# Arduino-Pro-Mini-CNC.net
KiCad netlist of a schematic drawn in EAGLE
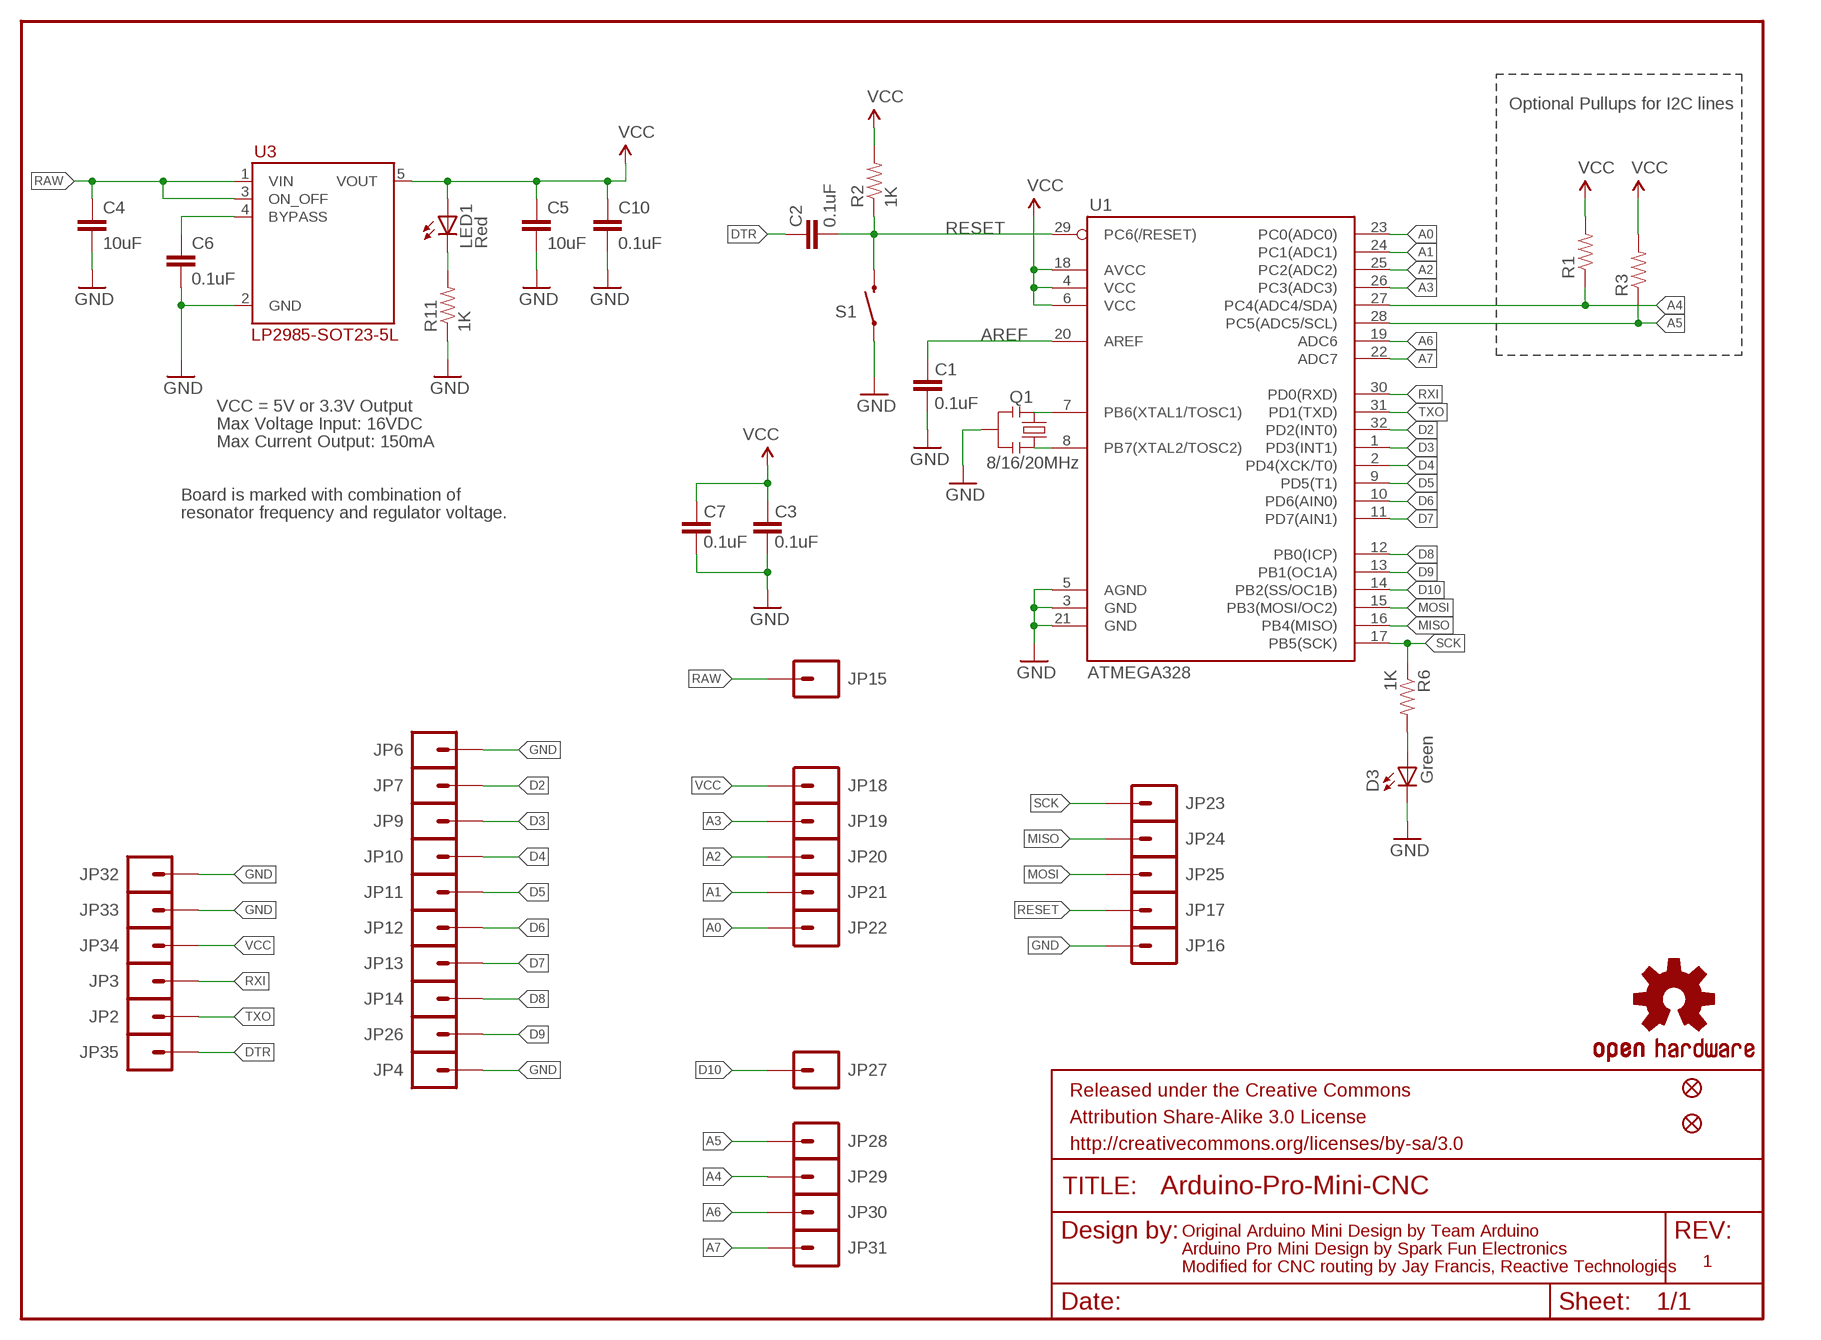
[diagram p0: schematic, sheet 1]

(export (version "E")
  (design (tool "Eeschema 10.0.6"))
  (components
    (comp (ref "C1")
      (value "0.1uF")
      (footprint "eagle-import:0603-CAP")
      (libsource (lib "eagle-import") (part "CAP0603-CAP"))
    )
    (comp (ref "C2")
      (value "0.1uF")
      (footprint "eagle-import:0603-CAP")
      (libsource (lib "eagle-import") (part "CAP0603-CAP"))
    )
    (comp (ref "C3")
      (value "0.1uF")
      (footprint "eagle-import:0603-CAP")
      (libsource (lib "eagle-import") (part "CAP0603-CAP"))
    )
    (comp (ref "C4")
      (value "10uF")
      (footprint "eagle-import:0603-CAP")
      (libsource (lib "eagle-import") (part "CAP0603-CAP"))
    )
    (comp (ref "C5")
      (value "10uF")
      (footprint "eagle-import:0603-CAP")
      (libsource (lib "eagle-import") (part "CAP0603-CAP"))
    )
    (comp (ref "C6")
      (value "0.1uF")
      (footprint "eagle-import:0603-CAP")
      (libsource (lib "eagle-import") (part "CAP0603-CAP"))
    )
    (comp (ref "C7")
      (value "0.1uF")
      (footprint "eagle-import:0603-CAP")
      (libsource (lib "eagle-import") (part "CAP0603-CAP"))
    )
    (comp (ref "C10")
      (value "0.1uF")
      (footprint "eagle-import:0603-CAP")
      (libsource (lib "eagle-import") (part "CAP0603-CAP"))
    )
    (comp (ref "D3")
      (value "Green")
      (footprint "eagle-import:0603-LED-ALT1")
      (libsource (lib "eagle-import") (part "LED"))
    )
    (comp (ref "FRAME1")
      (value "FRAME-LETTER")
      (footprint "eagle-import:CREATIVE_COMMONS")
      (libsource (lib "eagle-import") (part "FRAME-LETTER"))
    )
    (comp (ref "JP2")
      (value "M01SMD_160X40")
      (footprint "eagle-import:PAD-160-040")
      (libsource (lib "eagle-import") (part "M01SMD_160X40"))
    )
    (comp (ref "JP3")
      (value "M01SMD_160X40")
      (footprint "eagle-import:PAD-160-040")
      (libsource (lib "eagle-import") (part "M01SMD_160X40"))
    )
    (comp (ref "JP4")
      (value "M01SMD_160X40")
      (footprint "eagle-import:PAD-160-040")
      (libsource (lib "eagle-import") (part "M01SMD_160X40"))
    )
    (comp (ref "JP5")
      (value "FIDUCIALUFIDUCIAL")
      (footprint "eagle-import:MICRO-FIDUCIAL")
      (libsource (lib "eagle-import") (part "FIDUCIALUFIDUCIAL"))
    )
    (comp (ref "JP6")
      (value "M01SMD_160X40")
      (footprint "eagle-import:PAD-160-040")
      (libsource (lib "eagle-import") (part "M01SMD_160X40"))
    )
    (comp (ref "JP7")
      (value "M01SMD_160X40")
      (footprint "eagle-import:PAD-160-040")
      (libsource (lib "eagle-import") (part "M01SMD_160X40"))
    )
    (comp (ref "JP8")
      (value "FIDUCIALUFIDUCIAL")
      (footprint "eagle-import:MICRO-FIDUCIAL")
      (libsource (lib "eagle-import") (part "FIDUCIALUFIDUCIAL"))
    )
    (comp (ref "JP9")
      (value "M01SMD_160X40")
      (footprint "eagle-import:PAD-160-040")
      (libsource (lib "eagle-import") (part "M01SMD_160X40"))
    )
    (comp (ref "JP10")
      (value "M01SMD_160X40")
      (footprint "eagle-import:PAD-160-040")
      (libsource (lib "eagle-import") (part "M01SMD_160X40"))
    )
    (comp (ref "JP11")
      (value "M01SMD_160X40")
      (footprint "eagle-import:PAD-160-040")
      (libsource (lib "eagle-import") (part "M01SMD_160X40"))
    )
    (comp (ref "JP12")
      (value "M01SMD_160X40")
      (footprint "eagle-import:PAD-160-040")
      (libsource (lib "eagle-import") (part "M01SMD_160X40"))
    )
    (comp (ref "JP13")
      (value "M01SMD_160X40")
      (footprint "eagle-import:PAD-160-040")
      (libsource (lib "eagle-import") (part "M01SMD_160X40"))
    )
    (comp (ref "JP14")
      (value "M01SMD_160X40")
      (footprint "eagle-import:PAD-160-040")
      (libsource (lib "eagle-import") (part "M01SMD_160X40"))
    )
    (comp (ref "JP15")
      (value "M01SMD_160X40")
      (footprint "eagle-import:PAD-160-040")
      (libsource (lib "eagle-import") (part "M01SMD_160X40"))
    )
    (comp (ref "JP16")
      (value "M01SMD_160X40")
      (footprint "eagle-import:PAD-160-040")
      (libsource (lib "eagle-import") (part "M01SMD_160X40"))
    )
    (comp (ref "JP17")
      (value "M01SMD_160X40")
      (footprint "eagle-import:PAD-160-040")
      (libsource (lib "eagle-import") (part "M01SMD_160X40"))
    )
    (comp (ref "JP18")
      (value "M01SMD_160X40")
      (footprint "eagle-import:PAD-160-040")
      (libsource (lib "eagle-import") (part "M01SMD_160X40"))
    )
    (comp (ref "JP19")
      (value "M01SMD_160X40")
      (footprint "eagle-import:PAD-160-040")
      (libsource (lib "eagle-import") (part "M01SMD_160X40"))
    )
    (comp (ref "JP20")
      (value "M01SMD_160X40")
      (footprint "eagle-import:PAD-160-040")
      (libsource (lib "eagle-import") (part "M01SMD_160X40"))
    )
    (comp (ref "JP21")
      (value "M01SMD_160X40")
      (footprint "eagle-import:PAD-160-040")
      (libsource (lib "eagle-import") (part "M01SMD_160X40"))
    )
    (comp (ref "JP22")
      (value "M01SMD_160X40")
      (footprint "eagle-import:PAD-160-040")
      (libsource (lib "eagle-import") (part "M01SMD_160X40"))
    )
    (comp (ref "JP23")
      (value "M01SMD_160X40")
      (footprint "eagle-import:PAD-160-040")
      (libsource (lib "eagle-import") (part "M01SMD_160X40"))
    )
    (comp (ref "JP24")
      (value "M01SMD_160X40")
      (footprint "eagle-import:PAD-160-040")
      (libsource (lib "eagle-import") (part "M01SMD_160X40"))
    )
    (comp (ref "JP25")
      (value "M01SMD_160X40")
      (footprint "eagle-import:PAD-160-040")
      (libsource (lib "eagle-import") (part "M01SMD_160X40"))
    )
    (comp (ref "JP26")
      (value "M01SMD_160X40")
      (footprint "eagle-import:PAD-160-040")
      (libsource (lib "eagle-import") (part "M01SMD_160X40"))
    )
    (comp (ref "JP27")
      (value "M01SMD_160X40")
      (footprint "eagle-import:PAD-160-040")
      (libsource (lib "eagle-import") (part "M01SMD_160X40"))
    )
    (comp (ref "JP28")
      (value "M01SMD_160X40")
      (footprint "eagle-import:PAD-160-040")
      (libsource (lib "eagle-import") (part "M01SMD_160X40"))
    )
    (comp (ref "JP29")
      (value "M01SMD_160X40")
      (footprint "eagle-import:PAD-160-040")
      (libsource (lib "eagle-import") (part "M01SMD_160X40"))
    )
    (comp (ref "JP30")
      (value "M01SMD_160X40")
      (footprint "eagle-import:PAD-160-040")
      (libsource (lib "eagle-import") (part "M01SMD_160X40"))
    )
    (comp (ref "JP31")
      (value "M01SMD_160X40")
      (footprint "eagle-import:PAD-160-040")
      (libsource (lib "eagle-import") (part "M01SMD_160X40"))
    )
    (comp (ref "JP32")
      (value "M01SMD_160X40")
      (footprint "eagle-import:PAD-160-040")
      (libsource (lib "eagle-import") (part "M01SMD_160X40"))
    )
    (comp (ref "JP33")
      (value "M01SMD_160X40")
      (footprint "eagle-import:PAD-160-040")
      (libsource (lib "eagle-import") (part "M01SMD_160X40"))
    )
    (comp (ref "JP34")
      (value "M01SMD_160X40")
      (footprint "eagle-import:PAD-160-040")
      (libsource (lib "eagle-import") (part "M01SMD_160X40"))
    )
    (comp (ref "JP35")
      (value "M01SMD_160X40")
      (footprint "eagle-import:PAD-160-040")
      (libsource (lib "eagle-import") (part "M01SMD_160X40"))
    )
    (comp (ref "LED1")
      (value "Red")
      (footprint "eagle-import:0603-LED-ALT1")
      (libsource (lib "eagle-import") (part "LED"))
    )
    (comp (ref "Q1")
      (value "8/16/20MHz")
      (footprint "eagle-import:RESONATOR-SMD-1_1")
      (libsource (lib "eagle-import") (part "RESONATOR1{colon}1"))
    )
    (comp (ref "R1")
      (value "RESISTOR0603-RES")
      (footprint "eagle-import:0603-RES")
      (libsource (lib "eagle-import") (part "RESISTOR0603-RES"))
    )
    (comp (ref "R2")
      (value "1K")
      (footprint "eagle-import:0603-RES")
      (libsource (lib "eagle-import") (part "RESISTOR0603-RES"))
    )
    (comp (ref "R3")
      (value "RESISTOR0603-RES")
      (footprint "eagle-import:0603-RES")
      (libsource (lib "eagle-import") (part "RESISTOR0603-RES"))
    )
    (comp (ref "R6")
      (value "1K")
      (footprint "eagle-import:0603-RES")
      (libsource (lib "eagle-import") (part "RESISTOR0603-RES"))
    )
    (comp (ref "R11")
      (value "1K")
      (footprint "eagle-import:0603-RES")
      (libsource (lib "eagle-import") (part "RESISTOR0603-RES"))
    )
    (comp (ref "S1")
      (value "SWITCH-MOMENTARY-2-OMRON-B3U-1000P")
      (footprint "eagle-import:TACTILE-SWITCH-OMRON-B3U-1000P")
      (libsource (lib "eagle-import") (part "SWITCH-MOMENTARY-2-OMRON-B3U-1000P"))
    )
    (comp (ref "U$3")
      (value "OSHW-LOGOS")
      (footprint "eagle-import:OSHW-LOGO-S")
      (libsource (lib "eagle-import") (part "OSHW-LOGOS"))
    )
    (comp (ref "U1")
      (value "ATMEGA328")
      (footprint "eagle-import:TQFP32-08")
      (libsource (lib "eagle-import") (part "ATMEGA168"))
    )
    (comp (ref "U3")
      (value "LP2985-SOT23-5L")
      (footprint "eagle-import:SOT23-5L")
      (libsource (lib "eagle-import") (part "LP2985-SOT23-5L"))
    )
  )
  (nets
    (net (code "1") (name "/AREF") (class "Default")
      (node (ref "C1") (pin "2") (pinfunction "2_2") (pintype "passive"))
      (node (ref "U1") (pin "20") (pinfunction "AREF_20") (pintype "bidirectional"))
    )
    (net (code "2") (name "A0") (class "Default")
      (node (ref "JP22") (pin "P$1") (pinfunction "1_P$1") (pintype "passive"))
      (node (ref "U1") (pin "23") (pinfunction "PC0(ADC0)_23") (pintype "bidirectional"))
    )
    (net (code "3") (name "A1") (class "Default")
      (node (ref "JP21") (pin "P$1") (pinfunction "1_P$1") (pintype "passive"))
      (node (ref "U1") (pin "24") (pinfunction "PC1(ADC1)_24") (pintype "bidirectional"))
    )
    (net (code "4") (name "A2") (class "Default")
      (node (ref "JP20") (pin "P$1") (pinfunction "1_P$1") (pintype "passive"))
      (node (ref "U1") (pin "25") (pinfunction "PC2(ADC2)_25") (pintype "bidirectional"))
    )
    (net (code "5") (name "A3") (class "Default")
      (node (ref "JP19") (pin "P$1") (pinfunction "1_P$1") (pintype "passive"))
      (node (ref "U1") (pin "26") (pinfunction "PC3(ADC3)_26") (pintype "bidirectional"))
    )
    (net (code "6") (name "A4") (class "Default")
      (node (ref "JP29") (pin "P$1") (pinfunction "1_P$1") (pintype "passive"))
      (node (ref "R1") (pin "1") (pinfunction "1_1") (pintype "passive"))
      (node (ref "U1") (pin "27") (pinfunction "PC4(ADC4/SDA)_27") (pintype "bidirectional"))
    )
    (net (code "7") (name "A5") (class "Default")
      (node (ref "JP28") (pin "P$1") (pinfunction "1_P$1") (pintype "passive"))
      (node (ref "R3") (pin "1") (pinfunction "1_1") (pintype "passive"))
      (node (ref "U1") (pin "28") (pinfunction "PC5(ADC5/SCL)_28") (pintype "bidirectional"))
    )
    (net (code "8") (name "A6") (class "Default")
      (node (ref "JP30") (pin "P$1") (pinfunction "1_P$1") (pintype "passive"))
      (node (ref "U1") (pin "19") (pinfunction "ADC6_19") (pintype "bidirectional"))
    )
    (net (code "9") (name "A7") (class "Default")
      (node (ref "JP31") (pin "P$1") (pinfunction "1_P$1") (pintype "passive"))
      (node (ref "U1") (pin "22") (pinfunction "ADC7_22") (pintype "bidirectional"))
    )
    (net (code "10") (name "D2") (class "Default")
      (node (ref "JP7") (pin "P$1") (pinfunction "1_P$1") (pintype "passive"))
      (node (ref "U1") (pin "32") (pinfunction "PD2(INT0)_32") (pintype "bidirectional"))
    )
    (net (code "11") (name "D3") (class "Default")
      (node (ref "JP9") (pin "P$1") (pinfunction "1_P$1") (pintype "passive"))
      (node (ref "U1") (pin "1") (pinfunction "PD3(INT1)_1") (pintype "bidirectional"))
    )
    (net (code "12") (name "D4") (class "Default")
      (node (ref "JP10") (pin "P$1") (pinfunction "1_P$1") (pintype "passive"))
      (node (ref "U1") (pin "2") (pinfunction "PD4(XCK/T0)_2") (pintype "bidirectional"))
    )
    (net (code "13") (name "D5") (class "Default")
      (node (ref "JP11") (pin "P$1") (pinfunction "1_P$1") (pintype "passive"))
      (node (ref "U1") (pin "9") (pinfunction "PD5(T1)_9") (pintype "bidirectional"))
    )
    (net (code "14") (name "D6") (class "Default")
      (node (ref "JP12") (pin "P$1") (pinfunction "1_P$1") (pintype "passive"))
      (node (ref "U1") (pin "10") (pinfunction "PD6(AIN0)_10") (pintype "bidirectional"))
    )
    (net (code "15") (name "D7") (class "Default")
      (node (ref "JP13") (pin "P$1") (pinfunction "1_P$1") (pintype "passive"))
      (node (ref "U1") (pin "11") (pinfunction "PD7(AIN1)_11") (pintype "bidirectional"))
    )
    (net (code "16") (name "D8") (class "Default")
      (node (ref "JP14") (pin "P$1") (pinfunction "1_P$1") (pintype "passive"))
      (node (ref "U1") (pin "12") (pinfunction "PB0(ICP)_12") (pintype "bidirectional"))
    )
    (net (code "17") (name "D9") (class "Default")
      (node (ref "JP26") (pin "P$1") (pinfunction "1_P$1") (pintype "passive"))
      (node (ref "U1") (pin "13") (pinfunction "PB1(OC1A)_13") (pintype "bidirectional"))
    )
    (net (code "18") (name "D10") (class "Default")
      (node (ref "JP27") (pin "P$1") (pinfunction "1_P$1") (pintype "passive"))
      (node (ref "U1") (pin "14") (pinfunction "PB2(SS/OC1B)_14") (pintype "bidirectional"))
    )
    (net (code "19") (name "DTR") (class "Default")
      (node (ref "C2") (pin "2") (pinfunction "2_2") (pintype "passive"))
      (node (ref "JP35") (pin "P$1") (pinfunction "1_P$1") (pintype "passive"))
    )
    (net (code "20") (name "GND") (class "Default")
      (node (ref "C1") (pin "1") (pinfunction "1_1") (pintype "passive"))
      (node (ref "C10") (pin "2") (pinfunction "2_2") (pintype "passive"))
      (node (ref "C3") (pin "1") (pinfunction "1_1") (pintype "passive"))
      (node (ref "C4") (pin "2") (pinfunction "2_2") (pintype "passive"))
      (node (ref "C5") (pin "2") (pinfunction "2_2") (pintype "passive"))
      (node (ref "C6") (pin "2") (pinfunction "2_2") (pintype "passive"))
      (node (ref "C7") (pin "1") (pinfunction "1_1") (pintype "passive"))
      (node (ref "D3") (pin "C") (pinfunction "C_C") (pintype "passive"))
      (node (ref "JP16") (pin "P$1") (pinfunction "1_P$1") (pintype "passive"))
      (node (ref "JP32") (pin "P$1") (pinfunction "1_P$1") (pintype "passive"))
      (node (ref "JP33") (pin "P$1") (pinfunction "1_P$1") (pintype "passive"))
      (node (ref "JP4") (pin "P$1") (pinfunction "1_P$1") (pintype "passive"))
      (node (ref "JP6") (pin "P$1") (pinfunction "1_P$1") (pintype "passive"))
      (node (ref "Q1") (pin "2") (pinfunction "2_2") (pintype "passive"))
      (node (ref "R11") (pin "1") (pinfunction "1_1") (pintype "passive"))
      (node (ref "S1") (pin "P$1") (pinfunction "1_P$1") (pintype "passive"))
      (node (ref "U1") (pin "21") (pinfunction "GND_21") (pintype "bidirectional"))
      (node (ref "U1") (pin "3") (pinfunction "GND_3") (pintype "bidirectional"))
      (node (ref "U1") (pin "5") (pinfunction "AGND_5") (pintype "bidirectional"))
      (node (ref "U3") (pin "2") (pinfunction "GND_2") (pintype "passive"))
    )
    (net (code "21") (name "MISO") (class "Default")
      (node (ref "JP24") (pin "P$1") (pinfunction "1_P$1") (pintype "passive"))
      (node (ref "U1") (pin "16") (pinfunction "PB4(MISO)_16") (pintype "bidirectional"))
    )
    (net (code "22") (name "MOSI") (class "Default")
      (node (ref "JP25") (pin "P$1") (pinfunction "1_P$1") (pintype "passive"))
      (node (ref "U1") (pin "15") (pinfunction "PB3(MOSI/OC2)_15") (pintype "bidirectional"))
    )
    (net (code "23") (name "Net-(D3-PadA)") (class "Default")
      (node (ref "D3") (pin "A") (pinfunction "A_A") (pintype "passive"))
      (node (ref "R6") (pin "2") (pinfunction "2_2") (pintype "passive"))
    )
    (net (code "24") (name "Net-(LED1-PadC)") (class "Default")
      (node (ref "LED1") (pin "C") (pinfunction "C_C") (pintype "passive"))
      (node (ref "R11") (pin "2") (pinfunction "2_2") (pintype "passive"))
    )
    (net (code "25") (name "Net-(U1-PB6(XTAL1{slash}TOSC1))") (class "Default")
      (node (ref "Q1") (pin "1") (pinfunction "1_1") (pintype "passive"))
      (node (ref "U1") (pin "7") (pinfunction "PB6(XTAL1/TOSC1)_7") (pintype "bidirectional"))
    )
    (net (code "26") (name "Net-(U1-PB7(XTAL2{slash}TOSC2))") (class "Default")
      (node (ref "Q1") (pin "3") (pinfunction "3_3") (pintype "passive"))
      (node (ref "U1") (pin "8") (pinfunction "PB7(XTAL2/TOSC2)_8") (pintype "bidirectional"))
    )
    (net (code "27") (name "Net-(U3-BYPASS)") (class "Default")
      (node (ref "C6") (pin "1") (pinfunction "1_1") (pintype "passive"))
      (node (ref "U3") (pin "4") (pinfunction "BYPASS_4") (pintype "passive"))
    )
    (net (code "28") (name "RAW") (class "Default")
      (node (ref "C4") (pin "1") (pinfunction "1_1") (pintype "passive"))
      (node (ref "JP15") (pin "P$1") (pinfunction "1_P$1") (pintype "passive"))
      (node (ref "U3") (pin "1") (pinfunction "VIN_1") (pintype "passive"))
      (node (ref "U3") (pin "3") (pinfunction "ON_OFF_3") (pintype "passive"))
    )
    (net (code "29") (name "RESET") (class "Default")
      (node (ref "C2") (pin "1") (pinfunction "1_1") (pintype "passive"))
      (node (ref "JP17") (pin "P$1") (pinfunction "1_P$1") (pintype "passive"))
      (node (ref "R2") (pin "1") (pinfunction "1_1") (pintype "passive"))
      (node (ref "S1") (pin "P$2") (pinfunction "2_P$2") (pintype "passive"))
      (node (ref "U1") (pin "29") (pinfunction "PC6(/RESET)_29") (pintype "bidirectional"))
    )
    (net (code "30") (name "RXI") (class "Default")
      (node (ref "JP3") (pin "P$1") (pinfunction "1_P$1") (pintype "passive"))
      (node (ref "U1") (pin "30") (pinfunction "PD0(RXD)_30") (pintype "bidirectional"))
    )
    (net (code "31") (name "SCK") (class "Default")
      (node (ref "JP23") (pin "P$1") (pinfunction "1_P$1") (pintype "passive"))
      (node (ref "R6") (pin "1") (pinfunction "1_1") (pintype "passive"))
      (node (ref "U1") (pin "17") (pinfunction "PB5(SCK)_17") (pintype "bidirectional"))
    )
    (net (code "32") (name "TXO") (class "Default")
      (node (ref "JP2") (pin "P$1") (pinfunction "1_P$1") (pintype "passive"))
      (node (ref "U1") (pin "31") (pinfunction "PD1(TXD)_31") (pintype "bidirectional"))
    )
    (net (code "33") (name "VCC") (class "Default")
      (node (ref "C10") (pin "1") (pinfunction "1_1") (pintype "passive"))
      (node (ref "C3") (pin "2") (pinfunction "2_2") (pintype "passive"))
      (node (ref "C5") (pin "1") (pinfunction "1_1") (pintype "passive"))
      (node (ref "C7") (pin "2") (pinfunction "2_2") (pintype "passive"))
      (node (ref "JP18") (pin "P$1") (pinfunction "1_P$1") (pintype "passive"))
      (node (ref "JP34") (pin "P$1") (pinfunction "1_P$1") (pintype "passive"))
      (node (ref "LED1") (pin "A") (pinfunction "A_A") (pintype "passive"))
      (node (ref "R1") (pin "2") (pinfunction "2_2") (pintype "passive"))
      (node (ref "R2") (pin "2") (pinfunction "2_2") (pintype "passive"))
      (node (ref "R3") (pin "2") (pinfunction "2_2") (pintype "passive"))
      (node (ref "U1") (pin "18") (pinfunction "AVCC_18") (pintype "bidirectional"))
      (node (ref "U1") (pin "4") (pinfunction "VCC_4") (pintype "bidirectional"))
      (node (ref "U1") (pin "6") (pinfunction "VCC_6") (pintype "bidirectional"))
      (node (ref "U3") (pin "5") (pinfunction "VOUT_5") (pintype "passive"))
    )
  )
)
